# RowMicro11.net
KiCad netlist of a schematic drawn in EAGLE
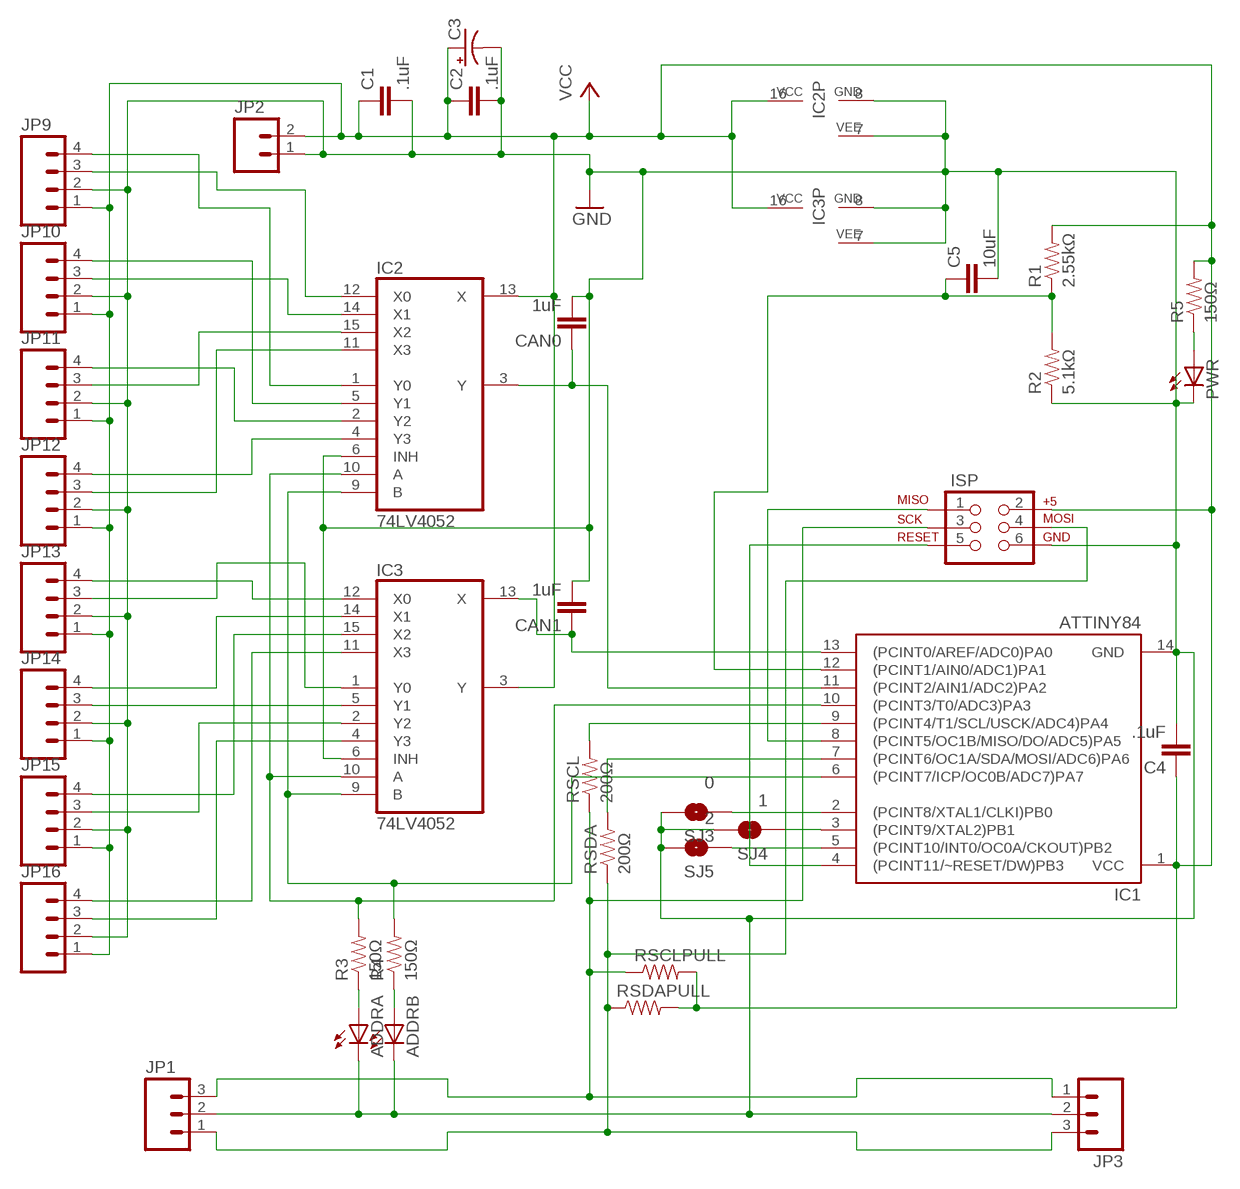
[diagram p0: schematic, sheet 1]

(export (version "E")
  (design (tool "Eeschema 10.0.6"))
  (components
    (comp (ref "ADDRA")
      (value "LED0603")
      (footprint "eagle-import:LED-0603")
      (libsource (lib "eagle-import") (part "LED0603"))
    )
    (comp (ref "ADDRB")
      (value "LED0603")
      (footprint "eagle-import:LED-0603")
      (libsource (lib "eagle-import") (part "LED0603"))
    )
    (comp (ref "C1")
      (value ".1uF")
      (footprint "eagle-import:0805")
      (libsource (lib "eagle-import") (part "CAP0805"))
    )
    (comp (ref "C2")
      (value ".1uF")
      (footprint "eagle-import:0805")
      (libsource (lib "eagle-import") (part "CAP0805"))
    )
    (comp (ref "C3")
      (value "CAP_POLPTH1")
      (footprint "eagle-import:CPOL-RADIAL-100UF-25V")
      (libsource (lib "eagle-import") (part "CAP_POLPTH1"))
    )
    (comp (ref "C4")
      (value ".1uF")
      (footprint "eagle-import:0805")
      (libsource (lib "eagle-import") (part "CAP0805"))
    )
    (comp (ref "C5")
      (value "10uF")
      (footprint "eagle-import:0805")
      (libsource (lib "eagle-import") (part "CAP0805"))
    )
    (comp (ref "CAN0")
      (value "1uF")
      (footprint "eagle-import:0805")
      (libsource (lib "eagle-import") (part "CAP0805"))
    )
    (comp (ref "CAN1")
      (value "1uF")
      (footprint "eagle-import:0805")
      (libsource (lib "eagle-import") (part "CAP0805"))
    )
    (comp (ref "IC1")
      (value "ATTINY84")
      (footprint "eagle-import:SO14")
      (libsource (lib "eagle-import") (part "ATTINY84"))
    )
    (comp (ref "IC2")
      (value "74LV4052")
      (footprint "eagle-import:TSSOP16L")
      (libsource (lib "eagle-import") (part "4052AL"))
    )
    (comp (ref "IC3")
      (value "74LV4052")
      (footprint "eagle-import:TSSOP16L")
      (libsource (lib "eagle-import") (part "4052AL"))
    )
    (comp (ref "ISP")
      (value "AVR_SPI_PRG_62X3_LOCK")
      (footprint "eagle-import:2X3_LOCK")
      (libsource (lib "eagle-import") (part "AVR_SPI_PRG_62X3_LOCK"))
    )
    (comp (ref "JP1")
      (value "M03SCREW")
      (footprint "eagle-import:SCREWTERMINAL-3.5MM-3")
      (libsource (lib "eagle-import") (part "M03SCREW"))
    )
    (comp (ref "JP2")
      (value "M02POLAR")
      (footprint "eagle-import:MOLEX-1X2")
      (libsource (lib "eagle-import") (part "M02POLAR"))
    )
    (comp (ref "JP3")
      (value "M03SCREW")
      (footprint "eagle-import:SCREWTERMINAL-3.5MM-3")
      (libsource (lib "eagle-import") (part "M03SCREW"))
    )
    (comp (ref "JP9")
      (value "M04POLAR")
      (footprint "eagle-import:MOLEX-1X4")
      (libsource (lib "eagle-import") (part "M04POLAR"))
    )
    (comp (ref "JP10")
      (value "M04POLAR")
      (footprint "eagle-import:MOLEX-1X4")
      (libsource (lib "eagle-import") (part "M04POLAR"))
    )
    (comp (ref "JP11")
      (value "M04POLAR")
      (footprint "eagle-import:MOLEX-1X4")
      (libsource (lib "eagle-import") (part "M04POLAR"))
    )
    (comp (ref "JP12")
      (value "M04POLAR")
      (footprint "eagle-import:MOLEX-1X4")
      (libsource (lib "eagle-import") (part "M04POLAR"))
    )
    (comp (ref "JP13")
      (value "M04POLAR")
      (footprint "eagle-import:MOLEX-1X4")
      (libsource (lib "eagle-import") (part "M04POLAR"))
    )
    (comp (ref "JP14")
      (value "M04POLAR")
      (footprint "eagle-import:MOLEX-1X4")
      (libsource (lib "eagle-import") (part "M04POLAR"))
    )
    (comp (ref "JP15")
      (value "M04POLAR")
      (footprint "eagle-import:MOLEX-1X4")
      (libsource (lib "eagle-import") (part "M04POLAR"))
    )
    (comp (ref "JP16")
      (value "M04POLAR")
      (footprint "eagle-import:MOLEX-1X4")
      (libsource (lib "eagle-import") (part "M04POLAR"))
    )
    (comp (ref "PWR")
      (value "LED0603")
      (footprint "eagle-import:LED-0603")
      (libsource (lib "eagle-import") (part "LED0603"))
    )
    (comp (ref "R1")
      (value "2.55kΩ")
      (footprint "eagle-import:0603-RES")
      (libsource (lib "eagle-import") (part "RESISTOR0603-RES"))
    )
    (comp (ref "R2")
      (value "5.1kΩ")
      (footprint "eagle-import:0603-RES")
      (libsource (lib "eagle-import") (part "RESISTOR0603-RES"))
    )
    (comp (ref "R3")
      (value "150Ω")
      (footprint "eagle-import:0603-RES")
      (libsource (lib "eagle-import") (part "RESISTOR0603-RES"))
    )
    (comp (ref "R4")
      (value "150Ω")
      (footprint "eagle-import:0603-RES")
      (libsource (lib "eagle-import") (part "RESISTOR0603-RES"))
    )
    (comp (ref "R5")
      (value "150Ω")
      (footprint "eagle-import:0603-RES")
      (libsource (lib "eagle-import") (part "RESISTOR0603-RES"))
    )
    (comp (ref "RSCL")
      (value "200Ω")
      (footprint "eagle-import:0603-RES")
      (libsource (lib "eagle-import") (part "RESISTOR0603-RES"))
    )
    (comp (ref "RSCLPULL")
      (value "RESISTOR0603-RES")
      (footprint "eagle-import:0603-RES")
      (libsource (lib "eagle-import") (part "RESISTOR0603-RES"))
    )
    (comp (ref "RSDA")
      (value "200Ω")
      (footprint "eagle-import:0603-RES")
      (libsource (lib "eagle-import") (part "RESISTOR0603-RES"))
    )
    (comp (ref "RSDAPULL")
      (value "RESISTOR0603-RES")
      (footprint "eagle-import:0603-RES")
      (libsource (lib "eagle-import") (part "RESISTOR0603-RES"))
    )
    (comp (ref "SJ3")
      (value "0")
      (footprint "eagle-import:SJ_2S-NO")
      (libsource (lib "eagle-import") (part "SOLDERJUMPERNO"))
    )
    (comp (ref "SJ4")
      (value "1")
      (footprint "eagle-import:SJ_2S-NO")
      (libsource (lib "eagle-import") (part "SOLDERJUMPERNO"))
    )
    (comp (ref "SJ5")
      (value "2")
      (footprint "eagle-import:SJ_2S-NO")
      (libsource (lib "eagle-import") (part "SOLDERJUMPERNO"))
    )
  )
  (nets
    (net (code "1") (name "GND") (class "Default")
      (node (ref "ADDRA") (pin "C") (pinfunction "C_C") (pintype "passive"))
      (node (ref "ADDRB") (pin "C") (pinfunction "C_C") (pintype "passive"))
      (node (ref "C1") (pin "2") (pinfunction "2_2") (pintype "passive"))
      (node (ref "C2") (pin "2") (pinfunction "2_2") (pintype "passive"))
      (node (ref "C3") (pin "2") (pinfunction "-_2") (pintype "passive"))
      (node (ref "C4") (pin "2") (pinfunction "2_2") (pintype "passive"))
      (node (ref "C5") (pin "2") (pinfunction "2_2") (pintype "passive"))
      (node (ref "CAN0") (pin "2") (pinfunction "2_2") (pintype "passive"))
      (node (ref "CAN1") (pin "2") (pinfunction "2_2") (pintype "passive"))
      (node (ref "IC1") (pin "14") (pinfunction "GND_14") (pintype "bidirectional"))
      (node (ref "IC2") (pin "6") (pinfunction "INH_6") (pintype "input"))
      (node (ref "IC2") (pin "7") (pinfunction "VEE_7") (pintype "power_in"))
      (node (ref "IC2") (pin "8") (pinfunction "GND_8") (pintype "power_in"))
      (node (ref "IC3") (pin "6") (pinfunction "INH_6") (pintype "input"))
      (node (ref "IC3") (pin "7") (pinfunction "VEE_7") (pintype "power_in"))
      (node (ref "IC3") (pin "8") (pinfunction "GND_8") (pintype "power_in"))
      (node (ref "ISP") (pin "6") (pinfunction "6_6") (pintype "passive"))
      (node (ref "JP1") (pin "2") (pinfunction "2_2") (pintype "passive"))
      (node (ref "JP10") (pin "2") (pinfunction "2_2") (pintype "passive"))
      (node (ref "JP11") (pin "2") (pinfunction "2_2") (pintype "passive"))
      (node (ref "JP12") (pin "2") (pinfunction "2_2") (pintype "passive"))
      (node (ref "JP13") (pin "2") (pinfunction "2_2") (pintype "passive"))
      (node (ref "JP14") (pin "2") (pinfunction "2_2") (pintype "passive"))
      (node (ref "JP15") (pin "2") (pinfunction "2_2") (pintype "passive"))
      (node (ref "JP16") (pin "2") (pinfunction "2_2") (pintype "passive"))
      (node (ref "JP2") (pin "1") (pinfunction "1_1") (pintype "passive"))
      (node (ref "JP3") (pin "2") (pinfunction "2_2") (pintype "passive"))
      (node (ref "JP9") (pin "2") (pinfunction "2_2") (pintype "passive"))
      (node (ref "PWR") (pin "C") (pinfunction "C_C") (pintype "passive"))
      (node (ref "R2") (pin "1") (pinfunction "1_1") (pintype "passive"))
      (node (ref "SJ3") (pin "2") (pinfunction "2_2") (pintype "passive"))
      (node (ref "SJ4") (pin "2") (pinfunction "2_2") (pintype "passive"))
      (node (ref "SJ5") (pin "2") (pinfunction "2_2") (pintype "passive"))
    )
    (net (code "2") (name "Net-(ADDRA-PadA)") (class "Default")
      (node (ref "ADDRA") (pin "A") (pinfunction "A_A") (pintype "passive"))
      (node (ref "R3") (pin "1") (pinfunction "1_1") (pintype "passive"))
    )
    (net (code "3") (name "Net-(ADDRB-PadA)") (class "Default")
      (node (ref "ADDRB") (pin "A") (pinfunction "A_A") (pintype "passive"))
      (node (ref "R4") (pin "1") (pinfunction "1_1") (pintype "passive"))
    )
    (net (code "4") (name "Net-(IC1-(PCINT0{slash}AREF{slash}ADC0)PA0)") (class "Default")
      (node (ref "CAN1") (pin "1") (pinfunction "1_1") (pintype "passive"))
      (node (ref "IC1") (pin "13") (pinfunction "(PCINT0/AREF/ADC0)PA0_13") (pintype "bidirectional"))
      (node (ref "IC3") (pin "13") (pinfunction "X_13") (pintype "bidirectional"))
    )
    (net (code "5") (name "Net-(IC1-(PCINT1{slash}AIN0{slash}ADC1)PA1)") (class "Default")
      (node (ref "C5") (pin "1") (pinfunction "1_1") (pintype "passive"))
      (node (ref "IC1") (pin "12") (pinfunction "(PCINT1/AIN0/ADC1)PA1_12") (pintype "bidirectional"))
      (node (ref "R1") (pin "1") (pinfunction "1_1") (pintype "passive"))
      (node (ref "R2") (pin "2") (pinfunction "2_2") (pintype "passive"))
    )
    (net (code "6") (name "Net-(IC1-(PCINT2{slash}AIN1{slash}ADC2)PA2)") (class "Default")
      (node (ref "CAN0") (pin "1") (pinfunction "1_1") (pintype "passive"))
      (node (ref "IC1") (pin "11") (pinfunction "(PCINT2/AIN1/ADC2)PA2_11") (pintype "bidirectional"))
      (node (ref "IC2") (pin "3") (pinfunction "Y_3") (pintype "bidirectional"))
    )
    (net (code "7") (name "Net-(IC1-(PCINT3{slash}T0{slash}ADC3)PA3)") (class "Default")
      (node (ref "IC1") (pin "10") (pinfunction "(PCINT3/T0/ADC3)PA3_10") (pintype "bidirectional"))
      (node (ref "IC2") (pin "10") (pinfunction "A_10") (pintype "input"))
      (node (ref "IC3") (pin "10") (pinfunction "A_10") (pintype "input"))
      (node (ref "R3") (pin "2") (pinfunction "2_2") (pintype "passive"))
    )
    (net (code "8") (name "Net-(IC1-(PCINT4{slash}T1{slash}SCL{slash}USCK{slash}ADC4)PA4)") (class "Default")
      (node (ref "IC1") (pin "9") (pinfunction "(PCINT4/T1/SCL/USCK/ADC4)PA4_9") (pintype "bidirectional"))
      (node (ref "RSCL") (pin "2") (pinfunction "2_2") (pintype "passive"))
    )
    (net (code "9") (name "Net-(IC1-(PCINT5{slash}OC1B{slash}MISO{slash}DO{slash}ADC5)PA5)") (class "Default")
      (node (ref "IC1") (pin "8") (pinfunction "(PCINT5/OC1B/MISO/DO/ADC5)PA5_8") (pintype "bidirectional"))
      (node (ref "ISP") (pin "1") (pinfunction "1_1") (pintype "passive"))
    )
    (net (code "10") (name "Net-(IC1-(PCINT6{slash}OC1A{slash}SDA{slash}MOSI{slash}ADC6)PA6)") (class "Default")
      (node (ref "IC1") (pin "7") (pinfunction "(PCINT6/OC1A/SDA/MOSI/ADC6)PA6_7") (pintype "bidirectional"))
      (node (ref "RSDA") (pin "2") (pinfunction "2_2") (pintype "passive"))
    )
    (net (code "11") (name "Net-(IC1-(PCINT7{slash}ICP{slash}OC0B{slash}ADC7)PA7)") (class "Default")
      (node (ref "IC1") (pin "6") (pinfunction "(PCINT7/ICP/OC0B/ADC7)PA7_6") (pintype "bidirectional"))
      (node (ref "IC2") (pin "9") (pinfunction "B_9") (pintype "input"))
      (node (ref "IC3") (pin "9") (pinfunction "B_9") (pintype "input"))
      (node (ref "R4") (pin "2") (pinfunction "2_2") (pintype "passive"))
    )
    (net (code "12") (name "Net-(IC1-(PCINT8{slash}XTAL1{slash}CLKI)PB0)") (class "Default")
      (node (ref "IC1") (pin "2") (pinfunction "(PCINT8/XTAL1/CLKI)PB0_2") (pintype "bidirectional"))
      (node (ref "SJ3") (pin "1") (pinfunction "1_1") (pintype "passive"))
    )
    (net (code "13") (name "Net-(IC1-(PCINT9{slash}XTAL2)PB1)") (class "Default")
      (node (ref "IC1") (pin "3") (pinfunction "(PCINT9/XTAL2)PB1_3") (pintype "bidirectional"))
      (node (ref "SJ4") (pin "1") (pinfunction "1_1") (pintype "passive"))
    )
    (net (code "14") (name "Net-(IC1-(PCINT10{slash}INT0{slash}OC0A{slash}CKOUT)PB2)") (class "Default")
      (node (ref "IC1") (pin "5") (pinfunction "(PCINT10/INT0/OC0A/CKOUT)PB2_5") (pintype "bidirectional"))
      (node (ref "SJ5") (pin "1") (pinfunction "1_1") (pintype "passive"))
    )
    (net (code "15") (name "Net-(IC1-(PCINT11{slash}~{RESET{slash}DW})PB3)") (class "Default")
      (node (ref "IC1") (pin "4") (pinfunction "(PCINT11/~{RESET/DW})PB3_4") (pintype "bidirectional"))
      (node (ref "ISP") (pin "5") (pinfunction "5_5") (pintype "passive"))
    )
    (net (code "16") (name "Net-(IC2A-X0)") (class "Default")
      (node (ref "IC2") (pin "12") (pinfunction "X0_12") (pintype "bidirectional"))
      (node (ref "JP9") (pin "3") (pinfunction "3_3") (pintype "passive"))
    )
    (net (code "17") (name "Net-(IC2A-X1)") (class "Default")
      (node (ref "IC2") (pin "14") (pinfunction "X1_14") (pintype "bidirectional"))
      (node (ref "JP10") (pin "3") (pinfunction "3_3") (pintype "passive"))
    )
    (net (code "18") (name "Net-(IC2A-X2)") (class "Default")
      (node (ref "IC2") (pin "15") (pinfunction "X2_15") (pintype "bidirectional"))
      (node (ref "JP11") (pin "3") (pinfunction "3_3") (pintype "passive"))
    )
    (net (code "19") (name "Net-(IC2A-X3)") (class "Default")
      (node (ref "IC2") (pin "11") (pinfunction "X3_11") (pintype "bidirectional"))
      (node (ref "JP12") (pin "3") (pinfunction "3_3") (pintype "passive"))
    )
    (net (code "20") (name "Net-(IC2A-Y0)") (class "Default")
      (node (ref "IC2") (pin "1") (pinfunction "Y0_1") (pintype "bidirectional"))
      (node (ref "JP9") (pin "4") (pinfunction "4_4") (pintype "passive"))
    )
    (net (code "21") (name "Net-(IC2A-Y1)") (class "Default")
      (node (ref "IC2") (pin "5") (pinfunction "Y1_5") (pintype "bidirectional"))
      (node (ref "JP10") (pin "4") (pinfunction "4_4") (pintype "passive"))
    )
    (net (code "22") (name "Net-(IC2A-Y2)") (class "Default")
      (node (ref "IC2") (pin "2") (pinfunction "Y2_2") (pintype "bidirectional"))
      (node (ref "JP11") (pin "4") (pinfunction "4_4") (pintype "passive"))
    )
    (net (code "23") (name "Net-(IC2A-Y3)") (class "Default")
      (node (ref "IC2") (pin "4") (pinfunction "Y3_4") (pintype "bidirectional"))
      (node (ref "JP12") (pin "4") (pinfunction "4_4") (pintype "passive"))
    )
    (net (code "24") (name "Net-(IC3A-X0)") (class "Default")
      (node (ref "IC3") (pin "12") (pinfunction "X0_12") (pintype "bidirectional"))
      (node (ref "JP13") (pin "4") (pinfunction "4_4") (pintype "passive"))
    )
    (net (code "25") (name "Net-(IC3A-X1)") (class "Default")
      (node (ref "IC3") (pin "14") (pinfunction "X1_14") (pintype "bidirectional"))
      (node (ref "JP14") (pin "4") (pinfunction "4_4") (pintype "passive"))
    )
    (net (code "26") (name "Net-(IC3A-X2)") (class "Default")
      (node (ref "IC3") (pin "15") (pinfunction "X2_15") (pintype "bidirectional"))
      (node (ref "JP15") (pin "4") (pinfunction "4_4") (pintype "passive"))
    )
    (net (code "27") (name "Net-(IC3A-X3)") (class "Default")
      (node (ref "IC3") (pin "11") (pinfunction "X3_11") (pintype "bidirectional"))
      (node (ref "JP16") (pin "4") (pinfunction "4_4") (pintype "passive"))
    )
    (net (code "28") (name "Net-(IC3A-Y0)") (class "Default")
      (node (ref "IC3") (pin "1") (pinfunction "Y0_1") (pintype "bidirectional"))
      (node (ref "JP13") (pin "3") (pinfunction "3_3") (pintype "passive"))
    )
    (net (code "29") (name "Net-(IC3A-Y1)") (class "Default")
      (node (ref "IC3") (pin "5") (pinfunction "Y1_5") (pintype "bidirectional"))
      (node (ref "JP14") (pin "3") (pinfunction "3_3") (pintype "passive"))
    )
    (net (code "30") (name "Net-(IC3A-Y2)") (class "Default")
      (node (ref "IC3") (pin "2") (pinfunction "Y2_2") (pintype "bidirectional"))
      (node (ref "JP15") (pin "3") (pinfunction "3_3") (pintype "passive"))
    )
    (net (code "31") (name "Net-(IC3A-Y3)") (class "Default")
      (node (ref "IC3") (pin "4") (pinfunction "Y3_4") (pintype "bidirectional"))
      (node (ref "JP16") (pin "3") (pinfunction "3_3") (pintype "passive"))
    )
    (net (code "32") (name "Net-(ISP-Pad3)") (class "Default")
      (node (ref "ISP") (pin "3") (pinfunction "3_3") (pintype "passive"))
      (node (ref "JP1") (pin "3") (pinfunction "3_3") (pintype "passive"))
      (node (ref "JP3") (pin "1") (pinfunction "1_1") (pintype "passive"))
      (node (ref "RSCL") (pin "1") (pinfunction "1_1") (pintype "passive"))
      (node (ref "RSCLPULL") (pin "1") (pinfunction "1_1") (pintype "passive"))
    )
    (net (code "33") (name "Net-(ISP-Pad4)") (class "Default")
      (node (ref "ISP") (pin "4") (pinfunction "4_4") (pintype "passive"))
      (node (ref "JP1") (pin "1") (pinfunction "1_1") (pintype "passive"))
      (node (ref "JP3") (pin "3") (pinfunction "3_3") (pintype "passive"))
      (node (ref "RSDA") (pin "1") (pinfunction "1_1") (pintype "passive"))
      (node (ref "RSDAPULL") (pin "1") (pinfunction "1_1") (pintype "passive"))
    )
    (net (code "34") (name "Net-(PWR-PadA)") (class "Default")
      (node (ref "PWR") (pin "A") (pinfunction "A_A") (pintype "passive"))
      (node (ref "R5") (pin "1") (pinfunction "1_1") (pintype "passive"))
    )
    (net (code "35") (name "VCC") (class "Default")
      (node (ref "C1") (pin "1") (pinfunction "1_1") (pintype "passive"))
      (node (ref "C2") (pin "1") (pinfunction "1_1") (pintype "passive"))
      (node (ref "C3") (pin "1") (pinfunction "+_1") (pintype "passive"))
      (node (ref "C4") (pin "1") (pinfunction "1_1") (pintype "passive"))
      (node (ref "IC1") (pin "1") (pinfunction "VCC_1") (pintype "bidirectional"))
      (node (ref "IC2") (pin "13") (pinfunction "X_13") (pintype "bidirectional"))
      (node (ref "IC2") (pin "16") (pinfunction "VCC_16") (pintype "power_in"))
      (node (ref "IC3") (pin "16") (pinfunction "VCC_16") (pintype "power_in"))
      (node (ref "IC3") (pin "3") (pinfunction "Y_3") (pintype "bidirectional"))
      (node (ref "ISP") (pin "2") (pinfunction "2_2") (pintype "passive"))
      (node (ref "JP10") (pin "1") (pinfunction "1_1") (pintype "passive"))
      (node (ref "JP11") (pin "1") (pinfunction "1_1") (pintype "passive"))
      (node (ref "JP12") (pin "1") (pinfunction "1_1") (pintype "passive"))
      (node (ref "JP13") (pin "1") (pinfunction "1_1") (pintype "passive"))
      (node (ref "JP14") (pin "1") (pinfunction "1_1") (pintype "passive"))
      (node (ref "JP15") (pin "1") (pinfunction "1_1") (pintype "passive"))
      (node (ref "JP16") (pin "1") (pinfunction "1_1") (pintype "passive"))
      (node (ref "JP2") (pin "2") (pinfunction "2_2") (pintype "passive"))
      (node (ref "JP9") (pin "1") (pinfunction "1_1") (pintype "passive"))
      (node (ref "R1") (pin "2") (pinfunction "2_2") (pintype "passive"))
      (node (ref "R5") (pin "2") (pinfunction "2_2") (pintype "passive"))
      (node (ref "RSCLPULL") (pin "2") (pinfunction "2_2") (pintype "passive"))
      (node (ref "RSDAPULL") (pin "2") (pinfunction "2_2") (pintype "passive"))
    )
  )
)
